# RGB_LEDs.net
KiCad netlist of a schematic drawn in Altium Designer
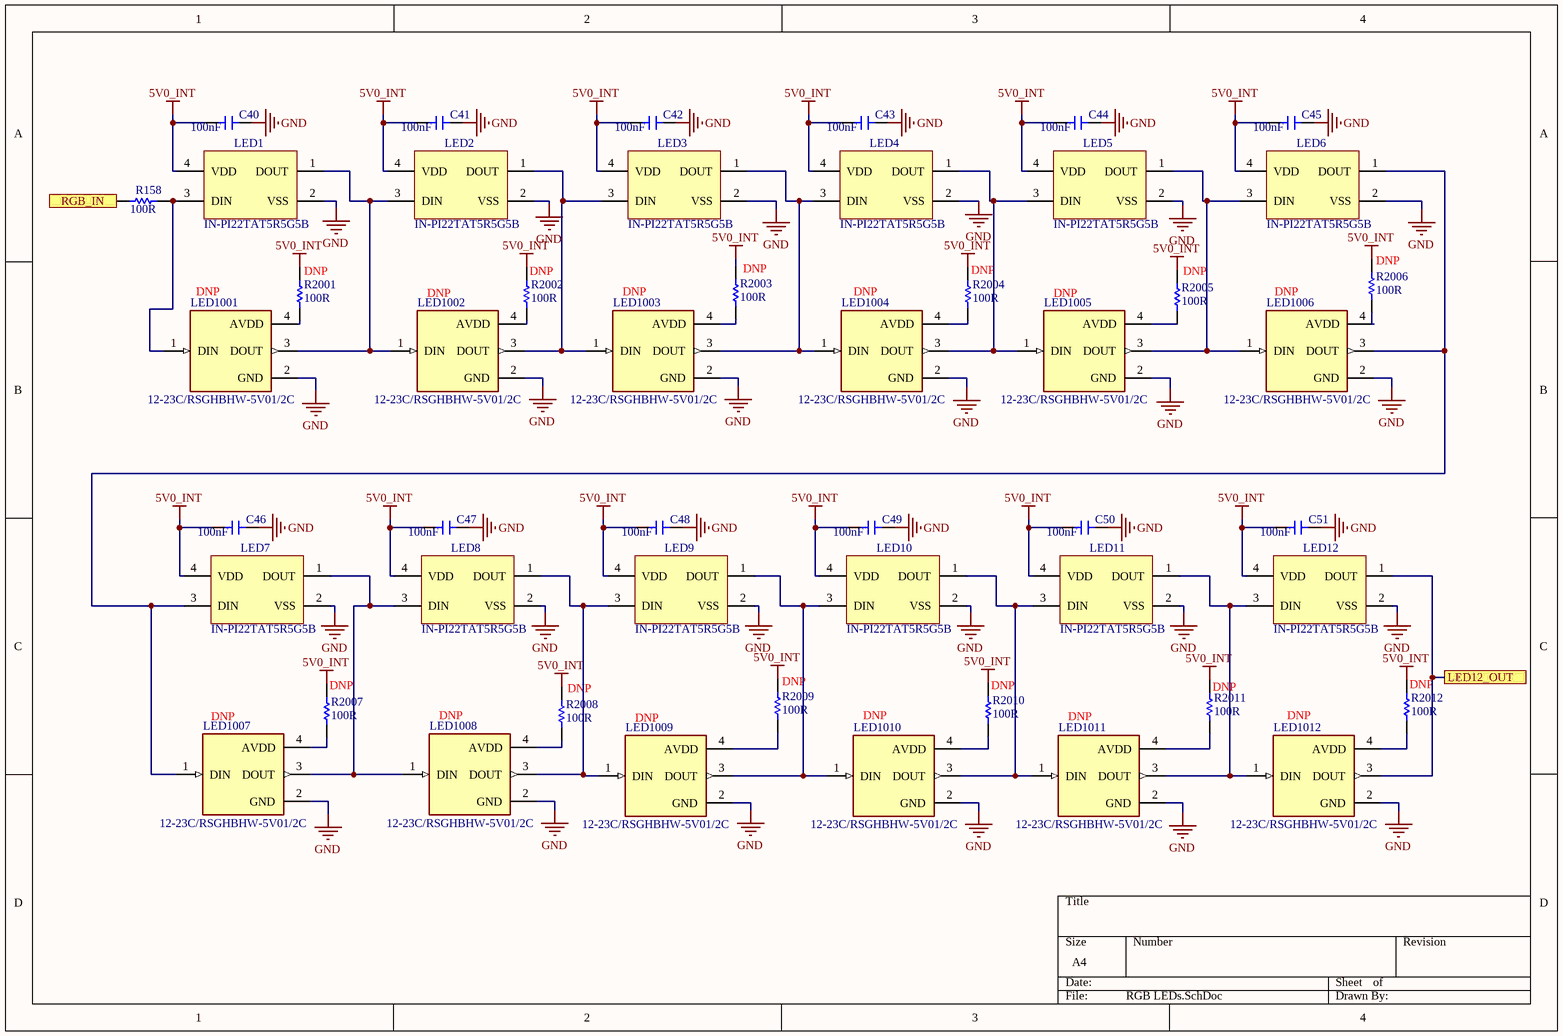
[diagram p0: RGB LEDs.SchDoc]

(export (version "E")
  (design (tool "Eeschema 10.0.6"))
  (components
    (comp (ref "C40")
      (value "100nF")
      (footprint "MareLux24Lib:CAP_0402_CER")
      (description "100nF 0402 Ceramic Capacitor")
      (fields (field (name "PART NUMBER") "CL05B104KP5NNNC") (field (name "VOLTAGE") "10V"))
      (libsource (lib "MareLux24Lib") (part "CAP_GEN_CER"))
    )
    (comp (ref "C41")
      (value "100nF")
      (footprint "MareLux24Lib:CAP_0402_CER")
      (description "100nF 0402 Ceramic Capacitor")
      (fields (field (name "PART NUMBER") "CL05B104KP5NNNC") (field (name "VOLTAGE") "10V"))
      (libsource (lib "MareLux24Lib") (part "CAP_GEN_CER"))
    )
    (comp (ref "C42")
      (value "100nF")
      (footprint "MareLux24Lib:CAP_0402_CER")
      (description "100nF 0402 Ceramic Capacitor")
      (fields (field (name "PART NUMBER") "CL05B104KP5NNNC") (field (name "VOLTAGE") "10V"))
      (libsource (lib "MareLux24Lib") (part "CAP_GEN_CER"))
    )
    (comp (ref "C43")
      (value "100nF")
      (footprint "MareLux24Lib:CAP_0402_CER")
      (description "100nF 0402 Ceramic Capacitor")
      (fields (field (name "PART NUMBER") "CL05B104KP5NNNC") (field (name "VOLTAGE") "10V"))
      (libsource (lib "MareLux24Lib") (part "CAP_GEN_CER"))
    )
    (comp (ref "C44")
      (value "100nF")
      (footprint "MareLux24Lib:CAP_0402_CER")
      (description "100nF 0402 Ceramic Capacitor")
      (fields (field (name "PART NUMBER") "CL05B104KP5NNNC") (field (name "VOLTAGE") "10V"))
      (libsource (lib "MareLux24Lib") (part "CAP_GEN_CER"))
    )
    (comp (ref "C45")
      (value "100nF")
      (footprint "MareLux24Lib:CAP_0402_CER")
      (description "100nF 0402 Ceramic Capacitor")
      (fields (field (name "PART NUMBER") "CL05B104KP5NNNC") (field (name "VOLTAGE") "10V"))
      (libsource (lib "MareLux24Lib") (part "CAP_GEN_CER"))
    )
    (comp (ref "C46")
      (value "100nF")
      (footprint "MareLux24Lib:CAP_0402_CER")
      (description "100nF 0402 Ceramic Capacitor")
      (fields (field (name "PART NUMBER") "CL05B104KP5NNNC") (field (name "VOLTAGE") "10V"))
      (libsource (lib "MareLux24Lib") (part "CAP_GEN_CER"))
    )
    (comp (ref "C47")
      (value "100nF")
      (footprint "MareLux24Lib:CAP_0402_CER")
      (description "100nF 0402 Ceramic Capacitor")
      (fields (field (name "PART NUMBER") "CL05B104KP5NNNC") (field (name "VOLTAGE") "10V"))
      (libsource (lib "MareLux24Lib") (part "CAP_GEN_CER"))
    )
    (comp (ref "C48")
      (value "100nF")
      (footprint "MareLux24Lib:CAP_0402_CER")
      (description "100nF 0402 Ceramic Capacitor")
      (fields (field (name "PART NUMBER") "CL05B104KP5NNNC") (field (name "VOLTAGE") "10V"))
      (libsource (lib "MareLux24Lib") (part "CAP_GEN_CER"))
    )
    (comp (ref "C49")
      (value "100nF")
      (footprint "MareLux24Lib:CAP_0402_CER")
      (description "100nF 0402 Ceramic Capacitor")
      (fields (field (name "PART NUMBER") "CL05B104KP5NNNC") (field (name "VOLTAGE") "10V"))
      (libsource (lib "MareLux24Lib") (part "CAP_GEN_CER"))
    )
    (comp (ref "C50")
      (value "100nF")
      (footprint "MareLux24Lib:CAP_0402_CER")
      (description "100nF 0402 Ceramic Capacitor")
      (fields (field (name "PART NUMBER") "CL05B104KP5NNNC") (field (name "VOLTAGE") "10V"))
      (libsource (lib "MareLux24Lib") (part "CAP_GEN_CER"))
    )
    (comp (ref "C51")
      (value "100nF")
      (footprint "MareLux24Lib:CAP_0402_CER")
      (description "100nF 0402 Ceramic Capacitor")
      (fields (field (name "PART NUMBER") "CL05B104KP5NNNC") (field (name "VOLTAGE") "10V"))
      (libsource (lib "MareLux24Lib") (part "CAP_GEN_CER"))
    )
    (comp (ref "LED1")
      (value "IN-PI22TAT5R5G5B")
      (footprint "RGB_IN-PI22TAT5R5G5B")
      (description "ADDRESS LED DISCRETE SERIAL RGB")
      (fields (field (name "MANUFACTURER") "Inolux"))
      (libsource (lib "MareLux24Lib") (part "IN-PI22TAT5R5G5B"))
    )
    (comp (ref "LED2")
      (value "IN-PI22TAT5R5G5B")
      (footprint "RGB_IN-PI22TAT5R5G5B")
      (description "ADDRESS LED DISCRETE SERIAL RGB")
      (fields (field (name "MANUFACTURER") "Inolux"))
      (libsource (lib "MareLux24Lib") (part "IN-PI22TAT5R5G5B"))
    )
    (comp (ref "LED3")
      (value "IN-PI22TAT5R5G5B")
      (footprint "RGB_IN-PI22TAT5R5G5B")
      (description "ADDRESS LED DISCRETE SERIAL RGB")
      (fields (field (name "MANUFACTURER") "Inolux"))
      (libsource (lib "MareLux24Lib") (part "IN-PI22TAT5R5G5B"))
    )
    (comp (ref "LED4")
      (value "IN-PI22TAT5R5G5B")
      (footprint "RGB_IN-PI22TAT5R5G5B")
      (description "ADDRESS LED DISCRETE SERIAL RGB")
      (fields (field (name "MANUFACTURER") "Inolux"))
      (libsource (lib "MareLux24Lib") (part "IN-PI22TAT5R5G5B"))
    )
    (comp (ref "LED5")
      (value "IN-PI22TAT5R5G5B")
      (footprint "RGB_IN-PI22TAT5R5G5B")
      (description "ADDRESS LED DISCRETE SERIAL RGB")
      (fields (field (name "MANUFACTURER") "Inolux"))
      (libsource (lib "MareLux24Lib") (part "IN-PI22TAT5R5G5B"))
    )
    (comp (ref "LED6")
      (value "IN-PI22TAT5R5G5B")
      (footprint "RGB_IN-PI22TAT5R5G5B")
      (description "ADDRESS LED DISCRETE SERIAL RGB")
      (fields (field (name "MANUFACTURER") "Inolux"))
      (libsource (lib "MareLux24Lib") (part "IN-PI22TAT5R5G5B"))
    )
    (comp (ref "LED7")
      (value "IN-PI22TAT5R5G5B")
      (footprint "RGB_IN-PI22TAT5R5G5B")
      (description "ADDRESS LED DISCRETE SERIAL RGB")
      (fields (field (name "MANUFACTURER") "Inolux"))
      (libsource (lib "MareLux24Lib") (part "IN-PI22TAT5R5G5B"))
    )
    (comp (ref "LED8")
      (value "IN-PI22TAT5R5G5B")
      (footprint "RGB_IN-PI22TAT5R5G5B")
      (description "ADDRESS LED DISCRETE SERIAL RGB")
      (fields (field (name "MANUFACTURER") "Inolux"))
      (libsource (lib "MareLux24Lib") (part "IN-PI22TAT5R5G5B"))
    )
    (comp (ref "LED9")
      (value "IN-PI22TAT5R5G5B")
      (footprint "RGB_IN-PI22TAT5R5G5B")
      (description "ADDRESS LED DISCRETE SERIAL RGB")
      (fields (field (name "MANUFACTURER") "Inolux"))
      (libsource (lib "MareLux24Lib") (part "IN-PI22TAT5R5G5B"))
    )
    (comp (ref "LED10")
      (value "IN-PI22TAT5R5G5B")
      (footprint "RGB_IN-PI22TAT5R5G5B")
      (description "ADDRESS LED DISCRETE SERIAL RGB")
      (fields (field (name "MANUFACTURER") "Inolux"))
      (libsource (lib "MareLux24Lib") (part "IN-PI22TAT5R5G5B"))
    )
    (comp (ref "LED11")
      (value "IN-PI22TAT5R5G5B")
      (footprint "RGB_IN-PI22TAT5R5G5B")
      (description "ADDRESS LED DISCRETE SERIAL RGB")
      (fields (field (name "MANUFACTURER") "Inolux"))
      (libsource (lib "MareLux24Lib") (part "IN-PI22TAT5R5G5B"))
    )
    (comp (ref "LED12")
      (value "IN-PI22TAT5R5G5B")
      (footprint "RGB_IN-PI22TAT5R5G5B")
      (description "ADDRESS LED DISCRETE SERIAL RGB")
      (fields (field (name "MANUFACTURER") "Inolux"))
      (libsource (lib "MareLux24Lib") (part "IN-PI22TAT5R5G5B"))
    )
    (comp (ref "LED1001")
      (value "12-23C/RSGHBHW-5V01/2C")
      (footprint "LED_12-23C/RSGHBHW-5V01/2C")
      (fields (field (name "MF") "Everlight Electronics Co Ltd") (field (name "PLACE") "DNP"))
      (libsource (lib "12-23C_RSGHBHW-5V01_2C") (part "12-23C/RSGHBHW-5V01/2C"))
    )
    (comp (ref "LED1002")
      (value "12-23C/RSGHBHW-5V01/2C")
      (footprint "LED_12-23C/RSGHBHW-5V01/2C")
      (fields (field (name "MF") "Everlight Electronics Co Ltd") (field (name "PLACE") "DNP"))
      (libsource (lib "12-23C_RSGHBHW-5V01_2C") (part "12-23C/RSGHBHW-5V01/2C"))
    )
    (comp (ref "LED1003")
      (value "12-23C/RSGHBHW-5V01/2C")
      (footprint "LED_12-23C/RSGHBHW-5V01/2C")
      (fields (field (name "MF") "Everlight Electronics Co Ltd") (field (name "PLACE") "DNP"))
      (libsource (lib "12-23C_RSGHBHW-5V01_2C") (part "12-23C/RSGHBHW-5V01/2C"))
    )
    (comp (ref "LED1004")
      (value "12-23C/RSGHBHW-5V01/2C")
      (footprint "LED_12-23C/RSGHBHW-5V01/2C")
      (fields (field (name "MF") "Everlight Electronics Co Ltd") (field (name "PLACE") "DNP"))
      (libsource (lib "12-23C_RSGHBHW-5V01_2C") (part "12-23C/RSGHBHW-5V01/2C"))
    )
    (comp (ref "LED1005")
      (value "12-23C/RSGHBHW-5V01/2C")
      (footprint "LED_12-23C/RSGHBHW-5V01/2C")
      (fields (field (name "MF") "Everlight Electronics Co Ltd") (field (name "PLACE") "DNP"))
      (libsource (lib "12-23C_RSGHBHW-5V01_2C") (part "12-23C/RSGHBHW-5V01/2C"))
    )
    (comp (ref "LED1006")
      (value "12-23C/RSGHBHW-5V01/2C")
      (footprint "LED_12-23C/RSGHBHW-5V01/2C")
      (fields (field (name "MF") "Everlight Electronics Co Ltd") (field (name "PLACE") "DNP"))
      (libsource (lib "12-23C_RSGHBHW-5V01_2C") (part "12-23C/RSGHBHW-5V01/2C"))
    )
    (comp (ref "LED1007")
      (value "12-23C/RSGHBHW-5V01/2C")
      (footprint "LED_12-23C/RSGHBHW-5V01/2C")
      (fields (field (name "MF") "Everlight Electronics Co Ltd") (field (name "PLACE") "DNP"))
      (libsource (lib "12-23C_RSGHBHW-5V01_2C") (part "12-23C/RSGHBHW-5V01/2C"))
    )
    (comp (ref "LED1008")
      (value "12-23C/RSGHBHW-5V01/2C")
      (footprint "LED_12-23C/RSGHBHW-5V01/2C")
      (fields (field (name "MF") "Everlight Electronics Co Ltd") (field (name "PLACE") "DNP"))
      (libsource (lib "12-23C_RSGHBHW-5V01_2C") (part "12-23C/RSGHBHW-5V01/2C"))
    )
    (comp (ref "LED1009")
      (value "12-23C/RSGHBHW-5V01/2C")
      (footprint "LED_12-23C/RSGHBHW-5V01/2C")
      (fields (field (name "MF") "Everlight Electronics Co Ltd") (field (name "PLACE") "DNP"))
      (libsource (lib "12-23C_RSGHBHW-5V01_2C") (part "12-23C/RSGHBHW-5V01/2C"))
    )
    (comp (ref "LED1010")
      (value "12-23C/RSGHBHW-5V01/2C")
      (footprint "LED_12-23C/RSGHBHW-5V01/2C")
      (fields (field (name "MF") "Everlight Electronics Co Ltd") (field (name "PLACE") "DNP"))
      (libsource (lib "12-23C_RSGHBHW-5V01_2C") (part "12-23C/RSGHBHW-5V01/2C"))
    )
    (comp (ref "LED1011")
      (value "12-23C/RSGHBHW-5V01/2C")
      (footprint "LED_12-23C/RSGHBHW-5V01/2C")
      (fields (field (name "MF") "Everlight Electronics Co Ltd") (field (name "PLACE") "DNP"))
      (libsource (lib "12-23C_RSGHBHW-5V01_2C") (part "12-23C/RSGHBHW-5V01/2C"))
    )
    (comp (ref "LED1012")
      (value "12-23C/RSGHBHW-5V01/2C")
      (footprint "LED_12-23C/RSGHBHW-5V01/2C")
      (fields (field (name "MF") "Everlight Electronics Co Ltd") (field (name "PLACE") "DNP"))
      (libsource (lib "12-23C_RSGHBHW-5V01_2C") (part "12-23C/RSGHBHW-5V01/2C"))
    )
    (comp (ref "R158")
      (value "100R")
      (footprint "MareLux24Lib:RES_0402_SMD")
      (description "Generic Chip Res 100R")
      (fields (field (name "PART NUMBER") "RMCF0402JT100R") (field (name "TOLERANCE") "5 %"))
      (libsource (lib "MareLux24Lib") (part "RES_GEN_SMD"))
    )
    (comp (ref "R2001")
      (value "100R")
      (footprint "MareLux24Lib:RES_0402_SMD")
      (description "Generic Chip Res 100R")
      (fields
        (field (name "PART NUMBER") "RMCF0402JT100R")
        (field (name "TOLERANCE") "5 %")
        (field (name "PLACE") "DNP")
      )
      (libsource (lib "MareLux24Lib") (part "RES_GEN_SMD"))
    )
    (comp (ref "R2002")
      (value "100R")
      (footprint "MareLux24Lib:RES_0402_SMD")
      (description "Generic Chip Res 100R")
      (fields
        (field (name "PART NUMBER") "RMCF0402JT100R")
        (field (name "TOLERANCE") "5 %")
        (field (name "PLACE") "DNP")
      )
      (libsource (lib "MareLux24Lib") (part "RES_GEN_SMD"))
    )
    (comp (ref "R2003")
      (value "100R")
      (footprint "MareLux24Lib:RES_0402_SMD")
      (description "Generic Chip Res 100R")
      (fields
        (field (name "PART NUMBER") "RMCF0402JT100R")
        (field (name "TOLERANCE") "5 %")
        (field (name "PLACE") "DNP")
      )
      (libsource (lib "MareLux24Lib") (part "RES_GEN_SMD"))
    )
    (comp (ref "R2004")
      (value "100R")
      (footprint "MareLux24Lib:RES_0402_SMD")
      (description "Generic Chip Res 100R")
      (fields
        (field (name "PART NUMBER") "RMCF0402JT100R")
        (field (name "TOLERANCE") "5 %")
        (field (name "PLACE") "DNP")
      )
      (libsource (lib "MareLux24Lib") (part "RES_GEN_SMD"))
    )
    (comp (ref "R2005")
      (value "100R")
      (footprint "MareLux24Lib:RES_0402_SMD")
      (description "Generic Chip Res 100R")
      (fields
        (field (name "PART NUMBER") "RMCF0402JT100R")
        (field (name "TOLERANCE") "5 %")
        (field (name "PLACE") "DNP")
      )
      (libsource (lib "MareLux24Lib") (part "RES_GEN_SMD"))
    )
    (comp (ref "R2006")
      (value "100R")
      (footprint "MareLux24Lib:RES_0402_SMD")
      (description "Generic Chip Res 100R")
      (fields
        (field (name "PART NUMBER") "RMCF0402JT100R")
        (field (name "TOLERANCE") "5 %")
        (field (name "PLACE") "DNP")
      )
      (libsource (lib "MareLux24Lib") (part "RES_GEN_SMD"))
    )
    (comp (ref "R2007")
      (value "100R")
      (footprint "MareLux24Lib:RES_0402_SMD")
      (description "Generic Chip Res 100R")
      (fields
        (field (name "PART NUMBER") "RMCF0402JT100R")
        (field (name "TOLERANCE") "5 %")
        (field (name "PLACE") "DNP")
      )
      (libsource (lib "MareLux24Lib") (part "RES_GEN_SMD"))
    )
    (comp (ref "R2008")
      (value "100R")
      (footprint "MareLux24Lib:RES_0402_SMD")
      (description "Generic Chip Res 100R")
      (fields
        (field (name "PART NUMBER") "RMCF0402JT100R")
        (field (name "TOLERANCE") "5 %")
        (field (name "PLACE") "DNP")
      )
      (libsource (lib "MareLux24Lib") (part "RES_GEN_SMD"))
    )
    (comp (ref "R2009")
      (value "100R")
      (footprint "MareLux24Lib:RES_0402_SMD")
      (description "Generic Chip Res 100R")
      (fields
        (field (name "PART NUMBER") "RMCF0402JT100R")
        (field (name "TOLERANCE") "5 %")
        (field (name "PLACE") "DNP")
      )
      (libsource (lib "MareLux24Lib") (part "RES_GEN_SMD"))
    )
    (comp (ref "R2010")
      (value "100R")
      (footprint "MareLux24Lib:RES_0402_SMD")
      (description "Generic Chip Res 100R")
      (fields
        (field (name "PART NUMBER") "RMCF0402JT100R")
        (field (name "TOLERANCE") "5 %")
        (field (name "PLACE") "DNP")
      )
      (libsource (lib "MareLux24Lib") (part "RES_GEN_SMD"))
    )
    (comp (ref "R2011")
      (value "100R")
      (footprint "MareLux24Lib:RES_0402_SMD")
      (description "Generic Chip Res 100R")
      (fields
        (field (name "PART NUMBER") "RMCF0402JT100R")
        (field (name "TOLERANCE") "5 %")
        (field (name "PLACE") "DNP")
      )
      (libsource (lib "MareLux24Lib") (part "RES_GEN_SMD"))
    )
    (comp (ref "R2012")
      (value "100R")
      (footprint "MareLux24Lib:RES_0402_SMD")
      (description "Generic Chip Res 100R")
      (fields
        (field (name "PART NUMBER") "RMCF0402JT100R")
        (field (name "TOLERANCE") "5 %")
        (field (name "PLACE") "DNP")
      )
      (libsource (lib "MareLux24Lib") (part "RES_GEN_SMD"))
    )
  )
  (nets
    (net (code "1") (name "/LED12_OUT") (class "Default")
      (node (ref "LED1012") (pin "3") (pinfunction "DOUT_3") (pintype "output"))
      (node (ref "LED12") (pin "1") (pinfunction "DOUT_1") (pintype "passive"))
    )
    (net (code "2") (name "/RGB_IN") (class "Default")
      (node (ref "R158") (pin "2") (pinfunction "2_2") (pintype "passive"))
    )
    (net (code "3") (name "5V0_INT") (class "Default")
      (node (ref "C40") (pin "2") (pinfunction "2_2") (pintype "passive"))
      (node (ref "C41") (pin "2") (pinfunction "2_2") (pintype "passive"))
      (node (ref "C42") (pin "2") (pinfunction "2_2") (pintype "passive"))
      (node (ref "C43") (pin "2") (pinfunction "2_2") (pintype "passive"))
      (node (ref "C44") (pin "2") (pinfunction "2_2") (pintype "passive"))
      (node (ref "C45") (pin "2") (pinfunction "2_2") (pintype "passive"))
      (node (ref "C46") (pin "2") (pinfunction "2_2") (pintype "passive"))
      (node (ref "C47") (pin "2") (pinfunction "2_2") (pintype "passive"))
      (node (ref "C48") (pin "2") (pinfunction "2_2") (pintype "passive"))
      (node (ref "C49") (pin "2") (pinfunction "2_2") (pintype "passive"))
      (node (ref "C50") (pin "2") (pinfunction "2_2") (pintype "passive"))
      (node (ref "C51") (pin "2") (pinfunction "2_2") (pintype "passive"))
      (node (ref "LED1") (pin "4") (pinfunction "VDD_4") (pintype "passive"))
      (node (ref "LED10") (pin "4") (pinfunction "VDD_4") (pintype "passive"))
      (node (ref "LED11") (pin "4") (pinfunction "VDD_4") (pintype "passive"))
      (node (ref "LED12") (pin "4") (pinfunction "VDD_4") (pintype "passive"))
      (node (ref "LED2") (pin "4") (pinfunction "VDD_4") (pintype "passive"))
      (node (ref "LED3") (pin "4") (pinfunction "VDD_4") (pintype "passive"))
      (node (ref "LED4") (pin "4") (pinfunction "VDD_4") (pintype "passive"))
      (node (ref "LED5") (pin "4") (pinfunction "VDD_4") (pintype "passive"))
      (node (ref "LED6") (pin "4") (pinfunction "VDD_4") (pintype "passive"))
      (node (ref "LED7") (pin "4") (pinfunction "VDD_4") (pintype "passive"))
      (node (ref "LED8") (pin "4") (pinfunction "VDD_4") (pintype "passive"))
      (node (ref "LED9") (pin "4") (pinfunction "VDD_4") (pintype "passive"))
      (node (ref "R2001") (pin "2") (pinfunction "2_2") (pintype "passive"))
      (node (ref "R2002") (pin "2") (pinfunction "2_2") (pintype "passive"))
      (node (ref "R2003") (pin "2") (pinfunction "2_2") (pintype "passive"))
      (node (ref "R2004") (pin "1") (pinfunction "1_1") (pintype "passive"))
      (node (ref "R2005") (pin "1") (pinfunction "1_1") (pintype "passive"))
      (node (ref "R2006") (pin "1") (pinfunction "1_1") (pintype "passive"))
      (node (ref "R2007") (pin "1") (pinfunction "1_1") (pintype "passive"))
      (node (ref "R2008") (pin "1") (pinfunction "1_1") (pintype "passive"))
      (node (ref "R2009") (pin "1") (pinfunction "1_1") (pintype "passive"))
      (node (ref "R2010") (pin "1") (pinfunction "1_1") (pintype "passive"))
      (node (ref "R2011") (pin "1") (pinfunction "1_1") (pintype "passive"))
      (node (ref "R2012") (pin "1") (pinfunction "1_1") (pintype "passive"))
    )
    (net (code "4") (name "GND") (class "Default")
      (node (ref "C40") (pin "1") (pinfunction "1_1") (pintype "passive"))
      (node (ref "C41") (pin "1") (pinfunction "1_1") (pintype "passive"))
      (node (ref "C42") (pin "1") (pinfunction "1_1") (pintype "passive"))
      (node (ref "C43") (pin "1") (pinfunction "1_1") (pintype "passive"))
      (node (ref "C44") (pin "1") (pinfunction "1_1") (pintype "passive"))
      (node (ref "C45") (pin "1") (pinfunction "1_1") (pintype "passive"))
      (node (ref "C46") (pin "1") (pinfunction "1_1") (pintype "passive"))
      (node (ref "C47") (pin "1") (pinfunction "1_1") (pintype "passive"))
      (node (ref "C48") (pin "1") (pinfunction "1_1") (pintype "passive"))
      (node (ref "C49") (pin "1") (pinfunction "1_1") (pintype "passive"))
      (node (ref "C50") (pin "1") (pinfunction "1_1") (pintype "passive"))
      (node (ref "C51") (pin "1") (pinfunction "1_1") (pintype "passive"))
      (node (ref "LED1") (pin "2") (pinfunction "VSS_2") (pintype "passive"))
      (node (ref "LED10") (pin "2") (pinfunction "VSS_2") (pintype "passive"))
      (node (ref "LED1001") (pin "2") (pinfunction "GND_2") (pintype "passive"))
      (node (ref "LED1002") (pin "2") (pinfunction "GND_2") (pintype "passive"))
      (node (ref "LED1003") (pin "2") (pinfunction "GND_2") (pintype "passive"))
      (node (ref "LED1004") (pin "2") (pinfunction "GND_2") (pintype "passive"))
      (node (ref "LED1005") (pin "2") (pinfunction "GND_2") (pintype "passive"))
      (node (ref "LED1006") (pin "2") (pinfunction "GND_2") (pintype "passive"))
      (node (ref "LED1007") (pin "2") (pinfunction "GND_2") (pintype "passive"))
      (node (ref "LED1008") (pin "2") (pinfunction "GND_2") (pintype "passive"))
      (node (ref "LED1009") (pin "2") (pinfunction "GND_2") (pintype "passive"))
      (node (ref "LED1010") (pin "2") (pinfunction "GND_2") (pintype "passive"))
      (node (ref "LED1011") (pin "2") (pinfunction "GND_2") (pintype "passive"))
      (node (ref "LED1012") (pin "2") (pinfunction "GND_2") (pintype "passive"))
      (node (ref "LED11") (pin "2") (pinfunction "VSS_2") (pintype "passive"))
      (node (ref "LED12") (pin "2") (pinfunction "VSS_2") (pintype "passive"))
      (node (ref "LED2") (pin "2") (pinfunction "VSS_2") (pintype "passive"))
      (node (ref "LED3") (pin "2") (pinfunction "VSS_2") (pintype "passive"))
      (node (ref "LED4") (pin "2") (pinfunction "VSS_2") (pintype "passive"))
      (node (ref "LED5") (pin "2") (pinfunction "VSS_2") (pintype "passive"))
      (node (ref "LED6") (pin "2") (pinfunction "VSS_2") (pintype "passive"))
      (node (ref "LED7") (pin "2") (pinfunction "VSS_2") (pintype "passive"))
      (node (ref "LED8") (pin "2") (pinfunction "VSS_2") (pintype "passive"))
      (node (ref "LED9") (pin "2") (pinfunction "VSS_2") (pintype "passive"))
    )
    (net (code "5") (name "Net-(LED1-DIN)") (class "Default")
      (node (ref "LED1") (pin "3") (pinfunction "DIN_3") (pintype "passive"))
      (node (ref "LED1001") (pin "1") (pinfunction "DIN_1") (pintype "input"))
      (node (ref "R158") (pin "1") (pinfunction "1_1") (pintype "passive"))
    )
    (net (code "6") (name "Net-(LED1-DOUT)") (class "Default")
      (node (ref "LED1") (pin "1") (pinfunction "DOUT_1") (pintype "passive"))
      (node (ref "LED1001") (pin "3") (pinfunction "DOUT_3") (pintype "output"))
      (node (ref "LED1002") (pin "1") (pinfunction "DIN_1") (pintype "input"))
      (node (ref "LED2") (pin "3") (pinfunction "DIN_3") (pintype "passive"))
    )
    (net (code "7") (name "Net-(LED10-DIN)") (class "Default")
      (node (ref "LED10") (pin "3") (pinfunction "DIN_3") (pintype "passive"))
      (node (ref "LED1009") (pin "3") (pinfunction "DOUT_3") (pintype "output"))
      (node (ref "LED1010") (pin "1") (pinfunction "DIN_1") (pintype "input"))
      (node (ref "LED9") (pin "1") (pinfunction "DOUT_1") (pintype "passive"))
    )
    (net (code "8") (name "Net-(LED10-DOUT)") (class "Default")
      (node (ref "LED10") (pin "1") (pinfunction "DOUT_1") (pintype "passive"))
      (node (ref "LED1010") (pin "3") (pinfunction "DOUT_3") (pintype "output"))
      (node (ref "LED1011") (pin "1") (pinfunction "DIN_1") (pintype "input"))
      (node (ref "LED11") (pin "3") (pinfunction "DIN_3") (pintype "passive"))
    )
    (net (code "9") (name "Net-(LED1001-AVDD)") (class "Default")
      (node (ref "LED1001") (pin "4") (pinfunction "AVDD_4") (pintype "power_in"))
      (node (ref "R2001") (pin "1") (pinfunction "1_1") (pintype "passive"))
    )
    (net (code "10") (name "Net-(LED1002-AVDD)") (class "Default")
      (node (ref "LED1002") (pin "4") (pinfunction "AVDD_4") (pintype "power_in"))
      (node (ref "R2002") (pin "1") (pinfunction "1_1") (pintype "passive"))
    )
    (net (code "11") (name "Net-(LED1002-DOUT)") (class "Default")
      (node (ref "LED1002") (pin "3") (pinfunction "DOUT_3") (pintype "output"))
      (node (ref "LED1003") (pin "1") (pinfunction "DIN_1") (pintype "input"))
      (node (ref "LED2") (pin "1") (pinfunction "DOUT_1") (pintype "passive"))
      (node (ref "LED3") (pin "3") (pinfunction "DIN_3") (pintype "passive"))
    )
    (net (code "12") (name "Net-(LED1003-AVDD)") (class "Default")
      (node (ref "LED1003") (pin "4") (pinfunction "AVDD_4") (pintype "power_in"))
      (node (ref "R2003") (pin "1") (pinfunction "1_1") (pintype "passive"))
    )
    (net (code "13") (name "Net-(LED1003-DOUT)") (class "Default")
      (node (ref "LED1003") (pin "3") (pinfunction "DOUT_3") (pintype "output"))
      (node (ref "LED1004") (pin "1") (pinfunction "DIN_1") (pintype "input"))
      (node (ref "LED3") (pin "1") (pinfunction "DOUT_1") (pintype "passive"))
      (node (ref "LED4") (pin "3") (pinfunction "DIN_3") (pintype "passive"))
    )
    (net (code "14") (name "Net-(LED1004-AVDD)") (class "Default")
      (node (ref "LED1004") (pin "4") (pinfunction "AVDD_4") (pintype "power_in"))
      (node (ref "R2004") (pin "2") (pinfunction "2_2") (pintype "passive"))
    )
    (net (code "15") (name "Net-(LED1004-DOUT)") (class "Default")
      (node (ref "LED1004") (pin "3") (pinfunction "DOUT_3") (pintype "output"))
      (node (ref "LED1005") (pin "1") (pinfunction "DIN_1") (pintype "input"))
      (node (ref "LED4") (pin "1") (pinfunction "DOUT_1") (pintype "passive"))
      (node (ref "LED5") (pin "3") (pinfunction "DIN_3") (pintype "passive"))
    )
    (net (code "16") (name "Net-(LED1005-AVDD)") (class "Default")
      (node (ref "LED1005") (pin "4") (pinfunction "AVDD_4") (pintype "power_in"))
      (node (ref "R2005") (pin "2") (pinfunction "2_2") (pintype "passive"))
    )
    (net (code "17") (name "Net-(LED1005-DOUT)") (class "Default")
      (node (ref "LED1005") (pin "3") (pinfunction "DOUT_3") (pintype "output"))
      (node (ref "LED1006") (pin "1") (pinfunction "DIN_1") (pintype "input"))
      (node (ref "LED5") (pin "1") (pinfunction "DOUT_1") (pintype "passive"))
      (node (ref "LED6") (pin "3") (pinfunction "DIN_3") (pintype "passive"))
    )
    (net (code "18") (name "Net-(LED1006-AVDD)") (class "Default")
      (node (ref "LED1006") (pin "4") (pinfunction "AVDD_4") (pintype "power_in"))
      (node (ref "R2006") (pin "2") (pinfunction "2_2") (pintype "passive"))
    )
    (net (code "19") (name "Net-(LED1006-DOUT)") (class "Default")
      (node (ref "LED1006") (pin "3") (pinfunction "DOUT_3") (pintype "output"))
      (node (ref "LED1007") (pin "1") (pinfunction "DIN_1") (pintype "input"))
      (node (ref "LED6") (pin "1") (pinfunction "DOUT_1") (pintype "passive"))
      (node (ref "LED7") (pin "3") (pinfunction "DIN_3") (pintype "passive"))
    )
    (net (code "20") (name "Net-(LED1007-AVDD)") (class "Default")
      (node (ref "LED1007") (pin "4") (pinfunction "AVDD_4") (pintype "power_in"))
      (node (ref "R2007") (pin "2") (pinfunction "2_2") (pintype "passive"))
    )
    (net (code "21") (name "Net-(LED1007-DOUT)") (class "Default")
      (node (ref "LED1007") (pin "3") (pinfunction "DOUT_3") (pintype "output"))
      (node (ref "LED1008") (pin "1") (pinfunction "DIN_1") (pintype "input"))
      (node (ref "LED7") (pin "1") (pinfunction "DOUT_1") (pintype "passive"))
      (node (ref "LED8") (pin "3") (pinfunction "DIN_3") (pintype "passive"))
    )
    (net (code "22") (name "Net-(LED1008-AVDD)") (class "Default")
      (node (ref "LED1008") (pin "4") (pinfunction "AVDD_4") (pintype "power_in"))
      (node (ref "R2008") (pin "2") (pinfunction "2_2") (pintype "passive"))
    )
    (net (code "23") (name "Net-(LED1008-DOUT)") (class "Default")
      (node (ref "LED1008") (pin "3") (pinfunction "DOUT_3") (pintype "output"))
      (node (ref "LED1009") (pin "1") (pinfunction "DIN_1") (pintype "input"))
      (node (ref "LED8") (pin "1") (pinfunction "DOUT_1") (pintype "passive"))
      (node (ref "LED9") (pin "3") (pinfunction "DIN_3") (pintype "passive"))
    )
    (net (code "24") (name "Net-(LED1009-AVDD)") (class "Default")
      (node (ref "LED1009") (pin "4") (pinfunction "AVDD_4") (pintype "power_in"))
      (node (ref "R2009") (pin "2") (pinfunction "2_2") (pintype "passive"))
    )
    (net (code "25") (name "Net-(LED1010-AVDD)") (class "Default")
      (node (ref "LED1010") (pin "4") (pinfunction "AVDD_4") (pintype "power_in"))
      (node (ref "R2010") (pin "2") (pinfunction "2_2") (pintype "passive"))
    )
    (net (code "26") (name "Net-(LED1011-AVDD)") (class "Default")
      (node (ref "LED1011") (pin "4") (pinfunction "AVDD_4") (pintype "power_in"))
      (node (ref "R2011") (pin "2") (pinfunction "2_2") (pintype "passive"))
    )
    (net (code "27") (name "Net-(LED1011-DOUT)") (class "Default")
      (node (ref "LED1011") (pin "3") (pinfunction "DOUT_3") (pintype "output"))
      (node (ref "LED1012") (pin "1") (pinfunction "DIN_1") (pintype "input"))
      (node (ref "LED11") (pin "1") (pinfunction "DOUT_1") (pintype "passive"))
      (node (ref "LED12") (pin "3") (pinfunction "DIN_3") (pintype "passive"))
    )
    (net (code "28") (name "Net-(LED1012-AVDD)") (class "Default")
      (node (ref "LED1012") (pin "4") (pinfunction "AVDD_4") (pintype "power_in"))
      (node (ref "R2012") (pin "2") (pinfunction "2_2") (pintype "passive"))
    )
  )
)
